# pmc1.net
KiCad netlist of a schematic drawn in EAGLE
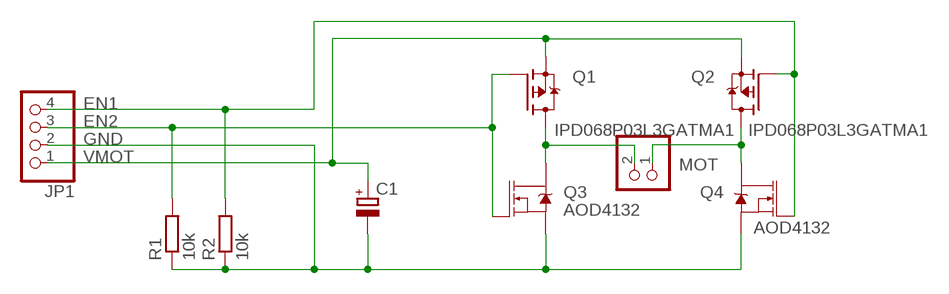
[diagram p0: schematic, sheet 1]

(export (version "E")
  (design (tool "Eeschema 10.0.6"))
  (components
    (comp (ref "C1")
      (value "CPOL-EUE5-13")
      (footprint "eagle-import:E5-13")
      (libsource (lib "eagle-import") (part "CPOL-EUE5-13"))
    )
    (comp (ref "JP1")
      (value "PINHD-1X4/90")
      (footprint "eagle-import:1X04_90")
      (libsource (lib "eagle-import") (part "PINHD-1X4/90"))
    )
    (comp (ref "MOT")
      (value "PINHD-1X2")
      (footprint "eagle-import:1X02")
      (libsource (lib "eagle-import") (part "PINHD-1X2"))
    )
    (comp (ref "Q1")
      (value "IPD068P03L3GATMA1")
      (footprint "eagle-import:TO252")
      (libsource (lib "eagle-import") (part "FDD4141TO252"))
    )
    (comp (ref "Q2")
      (value "IPD068P03L3GATMA1")
      (footprint "eagle-import:TO252")
      (libsource (lib "eagle-import") (part "FDD4141TO252"))
    )
    (comp (ref "Q3")
      (value "AOD4132")
      (footprint "eagle-import:DPAK")
      (libsource (lib "eagle-import") (part "MOSFET-NCH-FDD8780"))
    )
    (comp (ref "Q4")
      (value "AOD4132")
      (footprint "eagle-import:DPAK")
      (libsource (lib "eagle-import") (part "MOSFET-NCH-FDD8780"))
    )
    (comp (ref "R1")
      (value "10k")
      (footprint "eagle-import:R0603")
      (libsource (lib "eagle-import") (part "R-EU_R0603"))
    )
    (comp (ref "R2")
      (value "10k")
      (footprint "eagle-import:R0603")
      (libsource (lib "eagle-import") (part "R-EU_R0603"))
    )
  )
  (nets
    (net (code "1") (name "/EN1") (class "Default")
      (node (ref "JP1") (pin "4") (pinfunction "4_4") (pintype "passive"))
      (node (ref "Q2") (pin "1") (pinfunction "G_1") (pintype "passive"))
      (node (ref "Q4") (pin "1") (pinfunction "G_1") (pintype "bidirectional"))
      (node (ref "R2") (pin "2") (pinfunction "2_2") (pintype "passive"))
    )
    (net (code "2") (name "/EN2") (class "Default")
      (node (ref "JP1") (pin "3") (pinfunction "3_3") (pintype "passive"))
      (node (ref "Q1") (pin "1") (pinfunction "G_1") (pintype "passive"))
      (node (ref "Q3") (pin "1") (pinfunction "G_1") (pintype "bidirectional"))
      (node (ref "R1") (pin "2") (pinfunction "2_2") (pintype "passive"))
    )
    (net (code "3") (name "/GND") (class "Default")
      (node (ref "C1") (pin "-") (pinfunction "-_-") (pintype "passive"))
      (node (ref "JP1") (pin "2") (pinfunction "2_2") (pintype "passive"))
      (node (ref "Q3") (pin "3") (pinfunction "S_3") (pintype "bidirectional"))
      (node (ref "Q4") (pin "3") (pinfunction "S_3") (pintype "bidirectional"))
      (node (ref "R1") (pin "1") (pinfunction "1_1") (pintype "passive"))
      (node (ref "R2") (pin "1") (pinfunction "1_1") (pintype "passive"))
    )
    (net (code "4") (name "/VMOT") (class "Default")
      (node (ref "C1") (pin "+") (pinfunction "+_+") (pintype "passive"))
      (node (ref "JP1") (pin "1") (pinfunction "1_1") (pintype "passive"))
      (node (ref "Q1") (pin "2") (pinfunction "S_2") (pintype "passive"))
      (node (ref "Q2") (pin "2") (pinfunction "S_2") (pintype "passive"))
    )
    (net (code "5") (name "Net-(Q1-D)") (class "Default")
      (node (ref "MOT") (pin "2") (pinfunction "2_2") (pintype "passive"))
      (node (ref "Q1") (pin "3") (pinfunction "D_3") (pintype "passive"))
      (node (ref "Q3") (pin "4") (pinfunction "D_4") (pintype "bidirectional"))
    )
    (net (code "6") (name "Net-(Q2-D)") (class "Default")
      (node (ref "MOT") (pin "1") (pinfunction "1_1") (pintype "passive"))
      (node (ref "Q2") (pin "3") (pinfunction "D_3") (pintype "passive"))
      (node (ref "Q4") (pin "4") (pinfunction "D_4") (pintype "bidirectional"))
    )
  )
)
